# Light2021.net
KiCad netlist of a schematic drawn in EAGLE
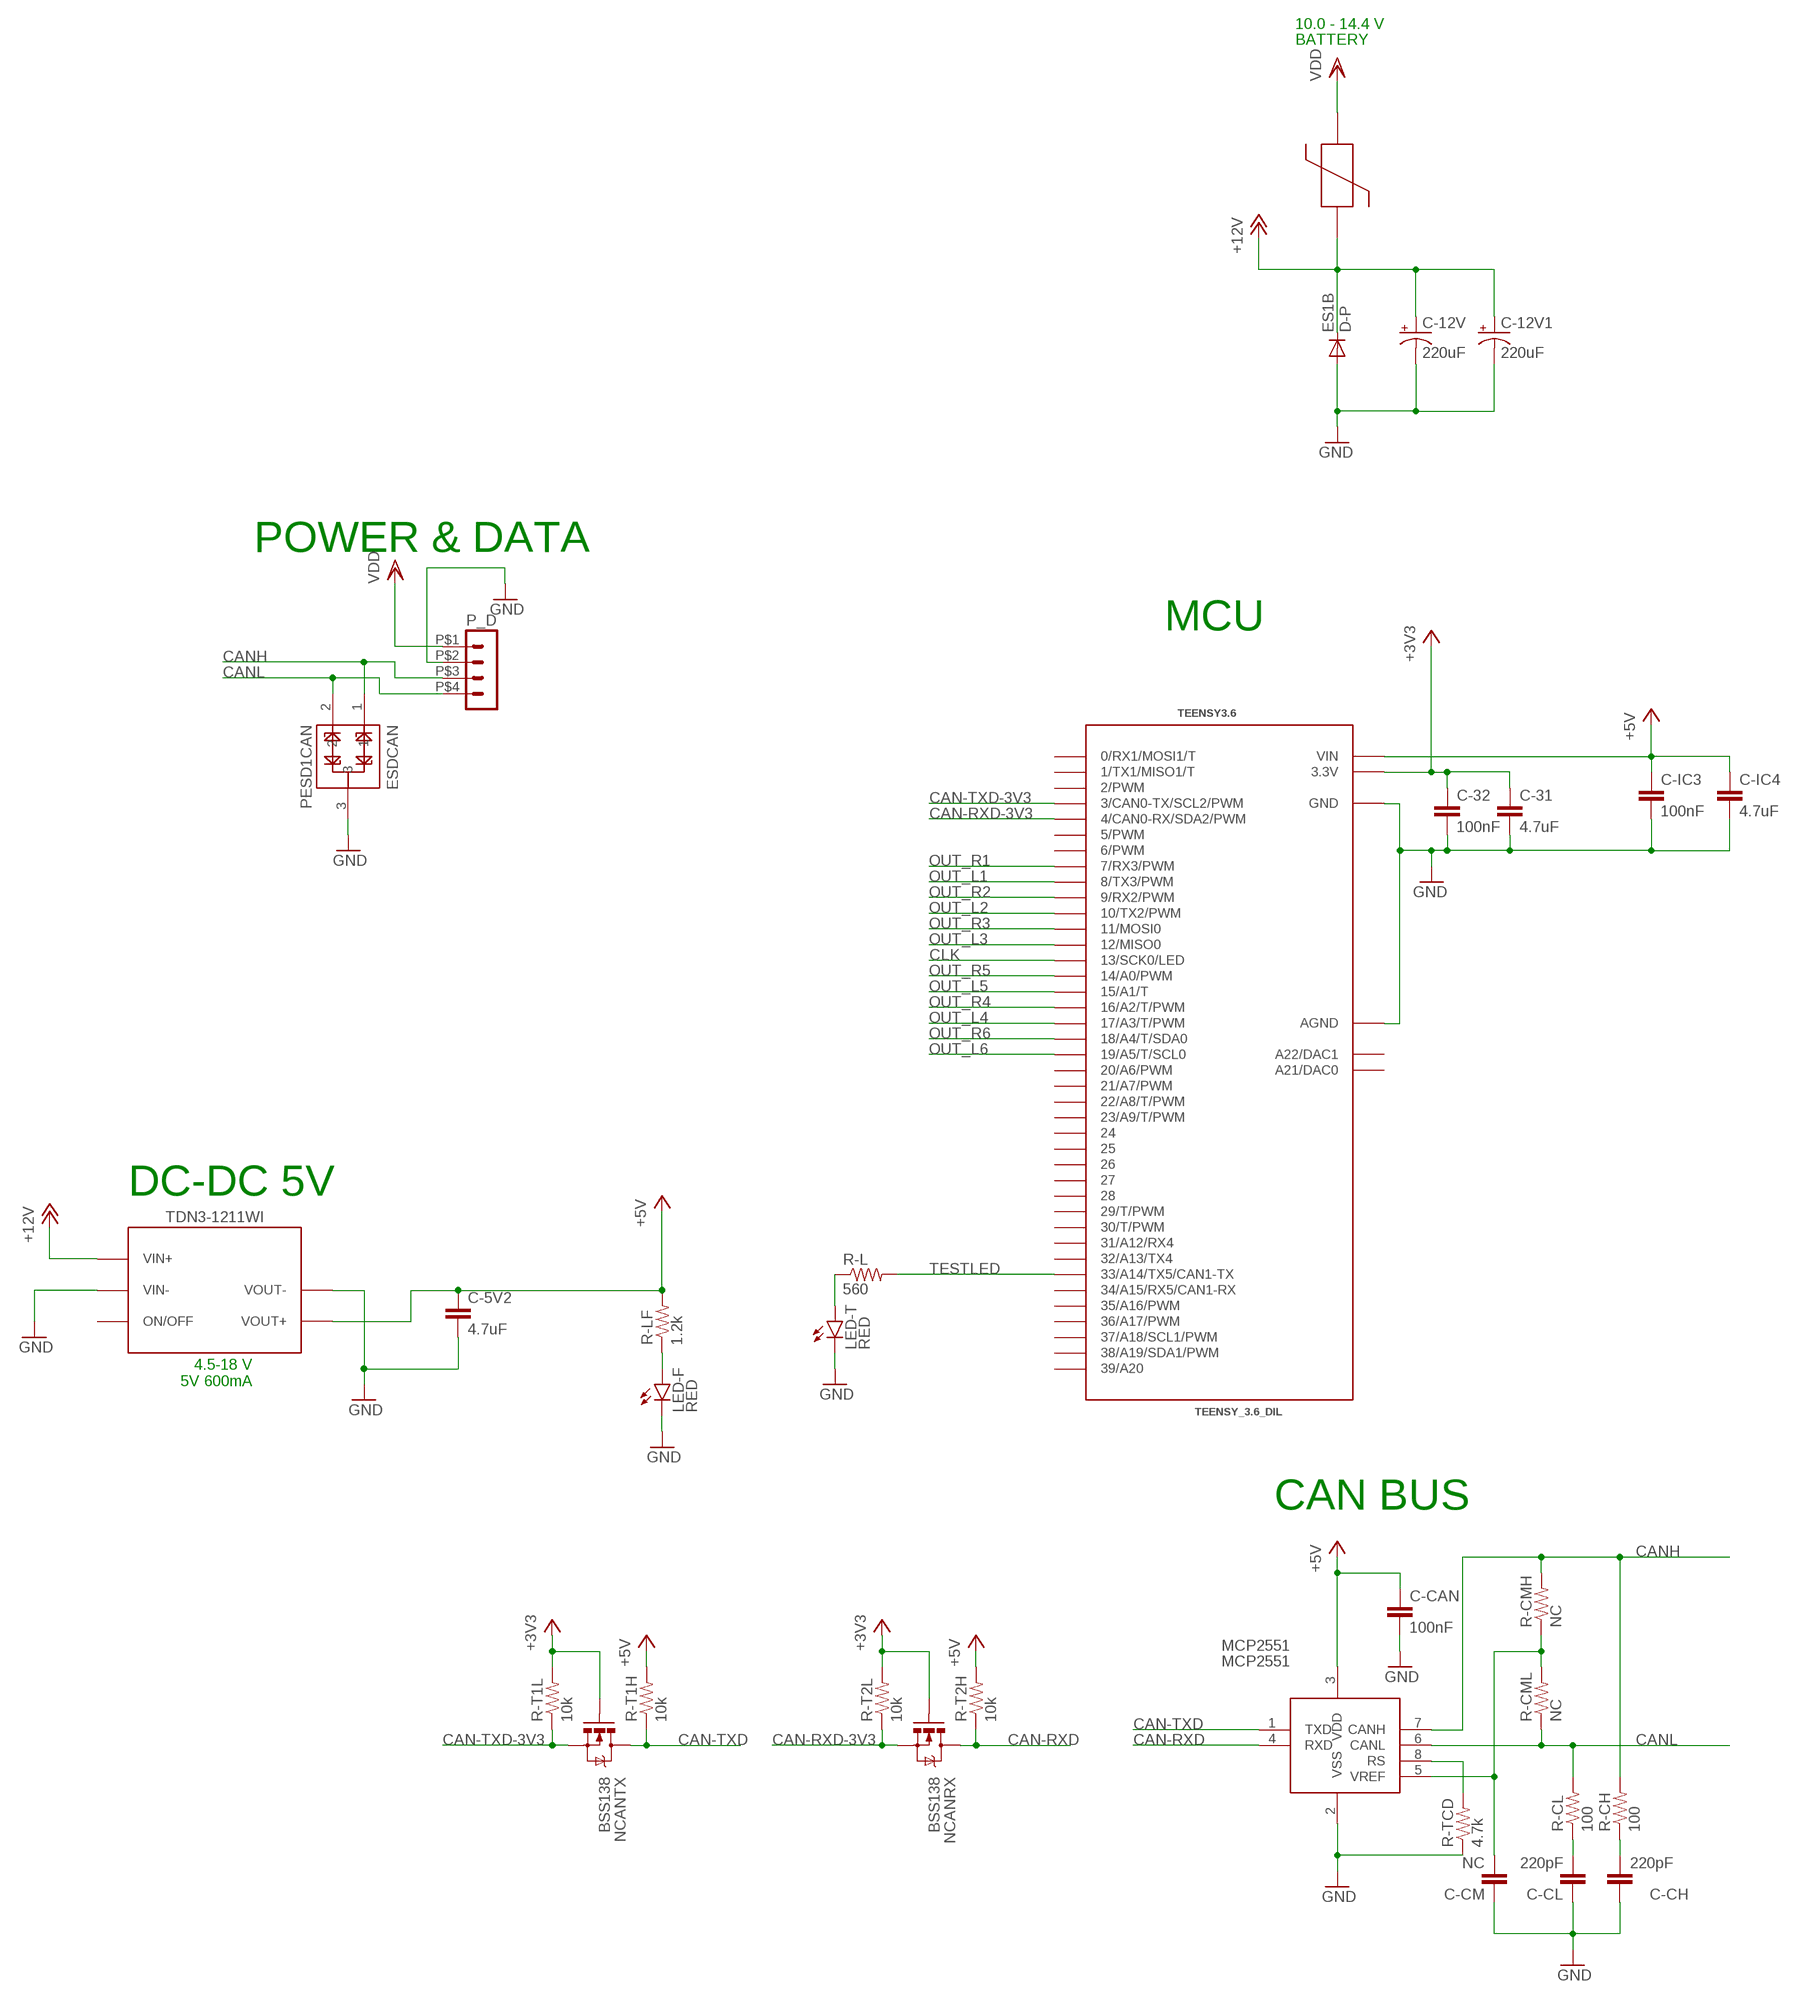
[diagram p0: schematic, sheet 1, part 1 of 2]
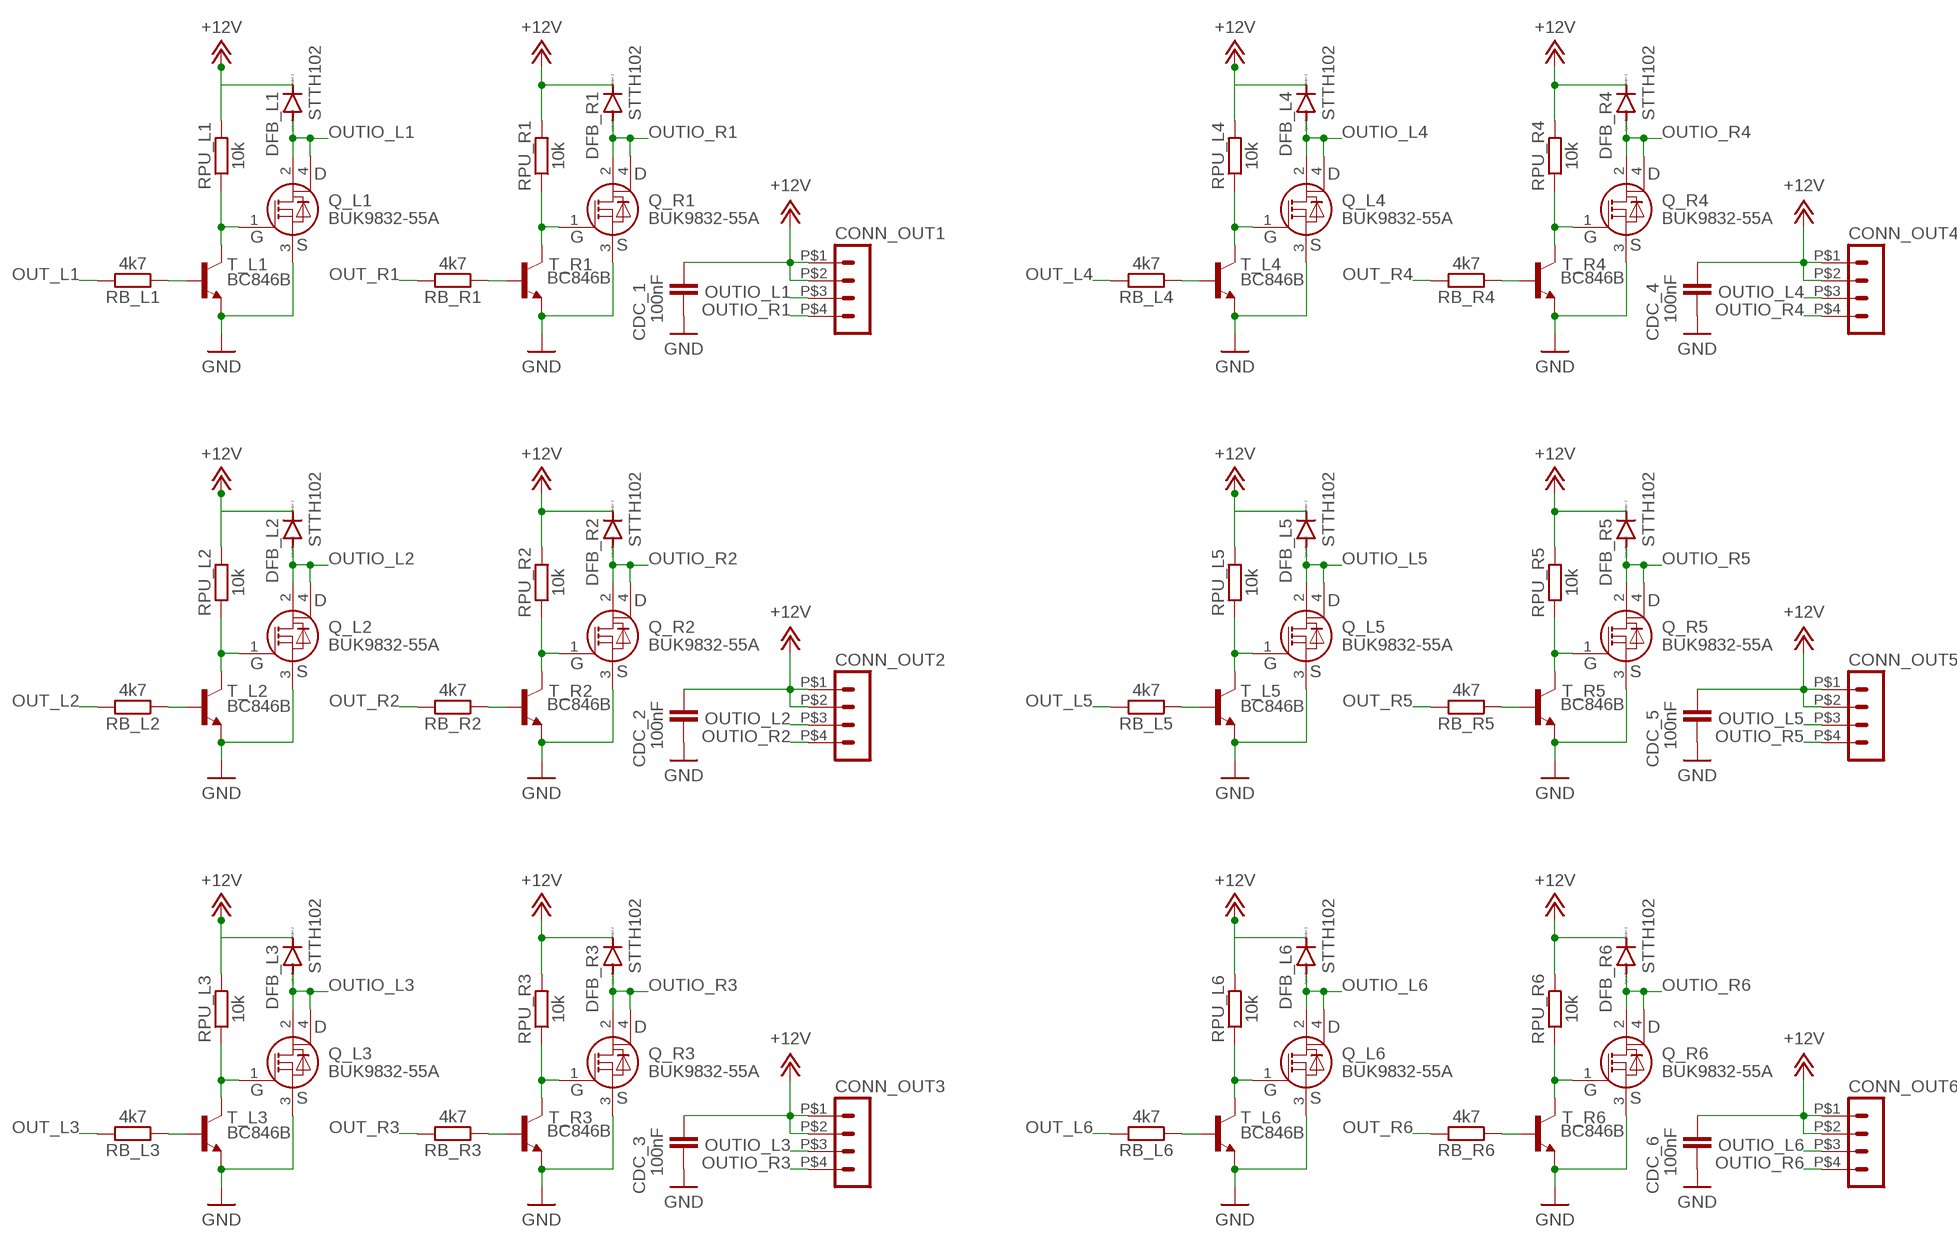
[diagram p1: schematic, sheet 1, part 2 of 2]

(export (version "E")
  (design (tool "Eeschema 10.0.6"))
  (components
    (comp (ref "C-5V2")
      (value "4.7uF")
      (footprint "eagle-import:1210")
      (libsource (lib "eagle-import") (part "CAP1210"))
    )
    (comp (ref "C-12V")
      (value "220uF")
      (footprint "eagle-import:PANASONIC_D")
      (libsource (lib "eagle-import") (part "CPOL-USD"))
    )
    (comp (ref "C-12V1")
      (value "220uF")
      (footprint "eagle-import:PANASONIC_D")
      (libsource (lib "eagle-import") (part "CPOL-USD"))
    )
    (comp (ref "C-31")
      (value "4.7uF")
      (footprint "eagle-import:1210")
      (libsource (lib "eagle-import") (part "CAP1210"))
    )
    (comp (ref "C-32")
      (value "100nF")
      (footprint "eagle-import:0805")
      (libsource (lib "eagle-import") (part "CAP0805"))
    )
    (comp (ref "C-CAN")
      (value "100nF")
      (footprint "eagle-import:0805")
      (libsource (lib "eagle-import") (part "CAP0805"))
    )
    (comp (ref "C-CH")
      (value "220pF")
      (footprint "eagle-import:0805")
      (libsource (lib "eagle-import") (part "CAP0805"))
    )
    (comp (ref "C-CL")
      (value "220pF")
      (footprint "eagle-import:0805")
      (libsource (lib "eagle-import") (part "CAP0805"))
    )
    (comp (ref "C-CM")
      (value "NC")
      (footprint "eagle-import:0805")
      (libsource (lib "eagle-import") (part "CAP0805"))
    )
    (comp (ref "C-IC3")
      (value "100nF")
      (footprint "eagle-import:0805")
      (libsource (lib "eagle-import") (part "CAP0805"))
    )
    (comp (ref "C-IC4")
      (value "4.7uF")
      (footprint "eagle-import:1210")
      (libsource (lib "eagle-import") (part "CAP1210"))
    )
    (comp (ref "CDC_1")
      (value "100nF")
      (footprint "eagle-import:0805")
      (libsource (lib "eagle-import") (part "CAP0805"))
    )
    (comp (ref "CDC_2")
      (value "100nF")
      (footprint "eagle-import:0805")
      (libsource (lib "eagle-import") (part "CAP0805"))
    )
    (comp (ref "CDC_3")
      (value "100nF")
      (footprint "eagle-import:0805")
      (libsource (lib "eagle-import") (part "CAP0805"))
    )
    (comp (ref "CDC_4")
      (value "100nF")
      (footprint "eagle-import:0805")
      (libsource (lib "eagle-import") (part "CAP0805"))
    )
    (comp (ref "CDC_5")
      (value "100nF")
      (footprint "eagle-import:0805")
      (libsource (lib "eagle-import") (part "CAP0805"))
    )
    (comp (ref "CDC_6")
      (value "100nF")
      (footprint "eagle-import:0805")
      (libsource (lib "eagle-import") (part "CAP0805"))
    )
    (comp (ref "CONN_OUT1")
      (value "HEADER_POS4_43045-0401")
      (footprint "eagle-import:43045-0400")
      (libsource (lib "eagle-import") (part "HEADER_POS4_?43045-0401"))
    )
    (comp (ref "CONN_OUT2")
      (value "HEADER_POS4_43045-0401")
      (footprint "eagle-import:43045-0400")
      (libsource (lib "eagle-import") (part "HEADER_POS4_?43045-0401"))
    )
    (comp (ref "CONN_OUT3")
      (value "HEADER_POS4_43045-0401")
      (footprint "eagle-import:43045-0400")
      (libsource (lib "eagle-import") (part "HEADER_POS4_?43045-0401"))
    )
    (comp (ref "CONN_OUT4")
      (value "HEADER_POS4_43045-0401")
      (footprint "eagle-import:43045-0400")
      (libsource (lib "eagle-import") (part "HEADER_POS4_?43045-0401"))
    )
    (comp (ref "CONN_OUT5")
      (value "HEADER_POS4_43045-0401")
      (footprint "eagle-import:43045-0400")
      (libsource (lib "eagle-import") (part "HEADER_POS4_?43045-0401"))
    )
    (comp (ref "CONN_OUT6")
      (value "HEADER_POS4_43045-0401")
      (footprint "eagle-import:43045-0400")
      (libsource (lib "eagle-import") (part "HEADER_POS4_?43045-0401"))
    )
    (comp (ref "D-P")
      (value "ES1B")
      (footprint "eagle-import:SMA-DIODE")
      (libsource (lib "eagle-import") (part "DIODESMA"))
    )
    (comp (ref "DFB_L1")
      (value "STTH102")
      (footprint "eagle-import:DO214AC")
      (libsource (lib "eagle-import") (part "DIODE-DO214AC"))
    )
    (comp (ref "DFB_L2")
      (value "STTH102")
      (footprint "eagle-import:DO214AC")
      (libsource (lib "eagle-import") (part "DIODE-DO214AC"))
    )
    (comp (ref "DFB_L3")
      (value "STTH102")
      (footprint "eagle-import:DO214AC")
      (libsource (lib "eagle-import") (part "DIODE-DO214AC"))
    )
    (comp (ref "DFB_L4")
      (value "STTH102")
      (footprint "eagle-import:DO214AC")
      (libsource (lib "eagle-import") (part "DIODE-DO214AC"))
    )
    (comp (ref "DFB_L5")
      (value "STTH102")
      (footprint "eagle-import:DO214AC")
      (libsource (lib "eagle-import") (part "DIODE-DO214AC"))
    )
    (comp (ref "DFB_L6")
      (value "STTH102")
      (footprint "eagle-import:DO214AC")
      (libsource (lib "eagle-import") (part "DIODE-DO214AC"))
    )
    (comp (ref "DFB_R1")
      (value "STTH102")
      (footprint "eagle-import:DO214AC")
      (libsource (lib "eagle-import") (part "DIODE-DO214AC"))
    )
    (comp (ref "DFB_R2")
      (value "STTH102")
      (footprint "eagle-import:DO214AC")
      (libsource (lib "eagle-import") (part "DIODE-DO214AC"))
    )
    (comp (ref "DFB_R3")
      (value "STTH102")
      (footprint "eagle-import:DO214AC")
      (libsource (lib "eagle-import") (part "DIODE-DO214AC"))
    )
    (comp (ref "DFB_R4")
      (value "STTH102")
      (footprint "eagle-import:DO214AC")
      (libsource (lib "eagle-import") (part "DIODE-DO214AC"))
    )
    (comp (ref "DFB_R5")
      (value "STTH102")
      (footprint "eagle-import:DO214AC")
      (libsource (lib "eagle-import") (part "DIODE-DO214AC"))
    )
    (comp (ref "DFB_R6")
      (value "STTH102")
      (footprint "eagle-import:DO214AC")
      (libsource (lib "eagle-import") (part "DIODE-DO214AC"))
    )
    (comp (ref "ESDCAN")
      (value "PESD1CAN")
      (footprint "eagle-import:SOT23-3")
      (libsource (lib "eagle-import") (part "PESD1CAN"))
    )
    (comp (ref "LED-F")
      (value "RED")
      (footprint "eagle-import:LED-1206")
      (libsource (lib "eagle-import") (part "LED1206"))
    )
    (comp (ref "LED-T")
      (value "RED")
      (footprint "eagle-import:LED-1206")
      (libsource (lib "eagle-import") (part "LED1206"))
    )
    (comp (ref "MAIN_FUSE")
      (value "SMF_OMNI-BLOK_FUSE_BLOCK")
      (footprint "eagle-import:SMF_OMNI-BLOK_FUSE_BLOCK")
      (libsource (lib "eagle-import") (part "SMF_OMNI-BLOK_FUSE_BLOCK"))
    )
    (comp (ref "MCP2551")
      (value "MCP2551")
      (footprint "eagle-import:SO-08M")
      (libsource (lib "eagle-import") (part "MCP2551"))
    )
    (comp (ref "NCANRX")
      (value "BSS138")
      (footprint "eagle-import:SOT23")
      (libsource (lib "eagle-import") (part "MOSFET-NCHANNELBSS123LT1G"))
    )
    (comp (ref "NCANTX")
      (value "BSS138")
      (footprint "eagle-import:SOT23")
      (libsource (lib "eagle-import") (part "MOSFET-NCHANNELBSS123LT1G"))
    )
    (comp (ref "P_D")
      (value "HEADER_POS4_43045-0401")
      (footprint "eagle-import:43045-0400")
      (libsource (lib "eagle-import") (part "HEADER_POS4_?43045-0401"))
    )
    (comp (ref "Q_L1")
      (value "BUK9832-55A")
      (footprint "eagle-import:SOT230P700X180-4N")
      (fields
        (field (name "MANUFACTURER_PART_NUMBER") "BUK9832-55A/CUX")
        (field (name "MOUSER_PART_NUMBER") "771-BUK9832-55A/CUX")
      )
      (libsource (lib "eagle-import") (part "BUK9832-55A"))
    )
    (comp (ref "Q_L2")
      (value "BUK9832-55A")
      (footprint "eagle-import:SOT230P700X180-4N")
      (fields
        (field (name "MANUFACTURER_PART_NUMBER") "BUK9832-55A/CUX")
        (field (name "MOUSER_PART_NUMBER") "771-BUK9832-55A/CUX")
      )
      (libsource (lib "eagle-import") (part "BUK9832-55A"))
    )
    (comp (ref "Q_L3")
      (value "BUK9832-55A")
      (footprint "eagle-import:SOT230P700X180-4N")
      (fields
        (field (name "MANUFACTURER_PART_NUMBER") "BUK9832-55A/CUX")
        (field (name "MOUSER_PART_NUMBER") "771-BUK9832-55A/CUX")
      )
      (libsource (lib "eagle-import") (part "BUK9832-55A"))
    )
    (comp (ref "Q_L4")
      (value "BUK9832-55A")
      (footprint "eagle-import:SOT230P700X180-4N")
      (fields
        (field (name "MANUFACTURER_PART_NUMBER") "BUK9832-55A/CUX")
        (field (name "MOUSER_PART_NUMBER") "771-BUK9832-55A/CUX")
      )
      (libsource (lib "eagle-import") (part "BUK9832-55A"))
    )
    (comp (ref "Q_L5")
      (value "BUK9832-55A")
      (footprint "eagle-import:SOT230P700X180-4N")
      (fields
        (field (name "MANUFACTURER_PART_NUMBER") "BUK9832-55A/CUX")
        (field (name "MOUSER_PART_NUMBER") "771-BUK9832-55A/CUX")
      )
      (libsource (lib "eagle-import") (part "BUK9832-55A"))
    )
    (comp (ref "Q_L6")
      (value "BUK9832-55A")
      (footprint "eagle-import:SOT230P700X180-4N")
      (fields
        (field (name "MANUFACTURER_PART_NUMBER") "BUK9832-55A/CUX")
        (field (name "MOUSER_PART_NUMBER") "771-BUK9832-55A/CUX")
      )
      (libsource (lib "eagle-import") (part "BUK9832-55A"))
    )
    (comp (ref "Q_R1")
      (value "BUK9832-55A")
      (footprint "eagle-import:SOT230P700X180-4N")
      (fields
        (field (name "MANUFACTURER_PART_NUMBER") "BUK9832-55A/CUX")
        (field (name "MOUSER_PART_NUMBER") "771-BUK9832-55A/CUX")
      )
      (libsource (lib "eagle-import") (part "BUK9832-55A"))
    )
    (comp (ref "Q_R2")
      (value "BUK9832-55A")
      (footprint "eagle-import:SOT230P700X180-4N")
      (fields
        (field (name "MANUFACTURER_PART_NUMBER") "BUK9832-55A/CUX")
        (field (name "MOUSER_PART_NUMBER") "771-BUK9832-55A/CUX")
      )
      (libsource (lib "eagle-import") (part "BUK9832-55A"))
    )
    (comp (ref "Q_R3")
      (value "BUK9832-55A")
      (footprint "eagle-import:SOT230P700X180-4N")
      (fields
        (field (name "MANUFACTURER_PART_NUMBER") "BUK9832-55A/CUX")
        (field (name "MOUSER_PART_NUMBER") "771-BUK9832-55A/CUX")
      )
      (libsource (lib "eagle-import") (part "BUK9832-55A"))
    )
    (comp (ref "Q_R4")
      (value "BUK9832-55A")
      (footprint "eagle-import:SOT230P700X180-4N")
      (fields
        (field (name "MANUFACTURER_PART_NUMBER") "BUK9832-55A/CUX")
        (field (name "MOUSER_PART_NUMBER") "771-BUK9832-55A/CUX")
      )
      (libsource (lib "eagle-import") (part "BUK9832-55A"))
    )
    (comp (ref "Q_R5")
      (value "BUK9832-55A")
      (footprint "eagle-import:SOT230P700X180-4N")
      (fields
        (field (name "MANUFACTURER_PART_NUMBER") "BUK9832-55A/CUX")
        (field (name "MOUSER_PART_NUMBER") "771-BUK9832-55A/CUX")
      )
      (libsource (lib "eagle-import") (part "BUK9832-55A"))
    )
    (comp (ref "Q_R6")
      (value "BUK9832-55A")
      (footprint "eagle-import:SOT230P700X180-4N")
      (fields
        (field (name "MANUFACTURER_PART_NUMBER") "BUK9832-55A/CUX")
        (field (name "MOUSER_PART_NUMBER") "771-BUK9832-55A/CUX")
      )
      (libsource (lib "eagle-import") (part "BUK9832-55A"))
    )
    (comp (ref "R-CH")
      (value "100")
      (footprint "eagle-import:0805")
      (libsource (lib "eagle-import") (part "RESISTOR0805"))
    )
    (comp (ref "R-CL")
      (value "100")
      (footprint "eagle-import:0805")
      (libsource (lib "eagle-import") (part "RESISTOR0805"))
    )
    (comp (ref "R-CMH")
      (value "NC")
      (footprint "eagle-import:0805")
      (libsource (lib "eagle-import") (part "RESISTOR0805"))
    )
    (comp (ref "R-CML")
      (value "NC")
      (footprint "eagle-import:0805")
      (libsource (lib "eagle-import") (part "RESISTOR0805"))
    )
    (comp (ref "R-L")
      (value "560")
      (footprint "eagle-import:0805")
      (libsource (lib "eagle-import") (part "RESISTOR0805"))
    )
    (comp (ref "R-LF")
      (value "1.2k")
      (footprint "eagle-import:0805")
      (libsource (lib "eagle-import") (part "RESISTOR0805"))
    )
    (comp (ref "R-T1H")
      (value "10k")
      (footprint "eagle-import:0805")
      (libsource (lib "eagle-import") (part "RESISTOR0805"))
    )
    (comp (ref "R-T1L")
      (value "10k")
      (footprint "eagle-import:0805")
      (libsource (lib "eagle-import") (part "RESISTOR0805"))
    )
    (comp (ref "R-T2H")
      (value "10k")
      (footprint "eagle-import:0805")
      (libsource (lib "eagle-import") (part "RESISTOR0805"))
    )
    (comp (ref "R-T2L")
      (value "10k")
      (footprint "eagle-import:0805")
      (libsource (lib "eagle-import") (part "RESISTOR0805"))
    )
    (comp (ref "R-TCD")
      (value "4.7k")
      (footprint "eagle-import:0805")
      (libsource (lib "eagle-import") (part "RESISTOR0805"))
    )
    (comp (ref "RB_L1")
      (value "4k7")
      (footprint "eagle-import:R0805")
      (libsource (lib "eagle-import") (part "R-EU_R0805"))
    )
    (comp (ref "RB_L2")
      (value "4k7")
      (footprint "eagle-import:R0805")
      (libsource (lib "eagle-import") (part "R-EU_R0805"))
    )
    (comp (ref "RB_L3")
      (value "4k7")
      (footprint "eagle-import:R0805")
      (libsource (lib "eagle-import") (part "R-EU_R0805"))
    )
    (comp (ref "RB_L4")
      (value "4k7")
      (footprint "eagle-import:R0805")
      (libsource (lib "eagle-import") (part "R-EU_R0805"))
    )
    (comp (ref "RB_L5")
      (value "4k7")
      (footprint "eagle-import:R0805")
      (libsource (lib "eagle-import") (part "R-EU_R0805"))
    )
    (comp (ref "RB_L6")
      (value "4k7")
      (footprint "eagle-import:R0805")
      (libsource (lib "eagle-import") (part "R-EU_R0805"))
    )
    (comp (ref "RB_R1")
      (value "4k7")
      (footprint "eagle-import:R0805")
      (libsource (lib "eagle-import") (part "R-EU_R0805"))
    )
    (comp (ref "RB_R2")
      (value "4k7")
      (footprint "eagle-import:R0805")
      (libsource (lib "eagle-import") (part "R-EU_R0805"))
    )
    (comp (ref "RB_R3")
      (value "4k7")
      (footprint "eagle-import:R0805")
      (libsource (lib "eagle-import") (part "R-EU_R0805"))
    )
    (comp (ref "RB_R4")
      (value "4k7")
      (footprint "eagle-import:R0805")
      (libsource (lib "eagle-import") (part "R-EU_R0805"))
    )
    (comp (ref "RB_R5")
      (value "4k7")
      (footprint "eagle-import:R0805")
      (libsource (lib "eagle-import") (part "R-EU_R0805"))
    )
    (comp (ref "RB_R6")
      (value "4k7")
      (footprint "eagle-import:R0805")
      (libsource (lib "eagle-import") (part "R-EU_R0805"))
    )
    (comp (ref "RPU_L1")
      (value "10k")
      (footprint "eagle-import:R0805")
      (libsource (lib "eagle-import") (part "R-EU_R0805"))
    )
    (comp (ref "RPU_L2")
      (value "10k")
      (footprint "eagle-import:R0805")
      (libsource (lib "eagle-import") (part "R-EU_R0805"))
    )
    (comp (ref "RPU_L3")
      (value "10k")
      (footprint "eagle-import:R0805")
      (libsource (lib "eagle-import") (part "R-EU_R0805"))
    )
    (comp (ref "RPU_L4")
      (value "10k")
      (footprint "eagle-import:R0805")
      (libsource (lib "eagle-import") (part "R-EU_R0805"))
    )
    (comp (ref "RPU_L5")
      (value "10k")
      (footprint "eagle-import:R0805")
      (libsource (lib "eagle-import") (part "R-EU_R0805"))
    )
    (comp (ref "RPU_L6")
      (value "10k")
      (footprint "eagle-import:R0805")
      (libsource (lib "eagle-import") (part "R-EU_R0805"))
    )
    (comp (ref "RPU_R1")
      (value "10k")
      (footprint "eagle-import:R0805")
      (libsource (lib "eagle-import") (part "R-EU_R0805"))
    )
    (comp (ref "RPU_R2")
      (value "10k")
      (footprint "eagle-import:R0805")
      (libsource (lib "eagle-import") (part "R-EU_R0805"))
    )
    (comp (ref "RPU_R3")
      (value "10k")
      (footprint "eagle-import:R0805")
      (libsource (lib "eagle-import") (part "R-EU_R0805"))
    )
    (comp (ref "RPU_R4")
      (value "10k")
      (footprint "eagle-import:R0805")
      (libsource (lib "eagle-import") (part "R-EU_R0805"))
    )
    (comp (ref "RPU_R5")
      (value "10k")
      (footprint "eagle-import:R0805")
      (libsource (lib "eagle-import") (part "R-EU_R0805"))
    )
    (comp (ref "RPU_R6")
      (value "10k")
      (footprint "eagle-import:R0805")
      (libsource (lib "eagle-import") (part "R-EU_R0805"))
    )
    (comp (ref "TDN3-1211WI")
      (value "TDN3WI")
      (footprint "eagle-import:TDC3WI")
      (libsource (lib "eagle-import") (part "TDN3WI"))
    )
    (comp (ref "TEENSY3.6")
      (value "TEENSY_3.6_DIL")
      (footprint "eagle-import:TEENSY_3.6_DIL")
      (libsource (lib "eagle-import") (part "TEENSY_3.6_DIL"))
    )
    (comp (ref "T_L1")
      (value "BC846B")
      (footprint "eagle-import:SOT23-BEC")
      (libsource (lib "eagle-import") (part "-NPN-SOT23-BECBC846B"))
    )
    (comp (ref "T_L2")
      (value "BC846B")
      (footprint "eagle-import:SOT23-BEC")
      (libsource (lib "eagle-import") (part "-NPN-SOT23-BECBC846B"))
    )
    (comp (ref "T_L3")
      (value "BC846B")
      (footprint "eagle-import:SOT23-BEC")
      (libsource (lib "eagle-import") (part "-NPN-SOT23-BECBC846B"))
    )
    (comp (ref "T_L4")
      (value "BC846B")
      (footprint "eagle-import:SOT23-BEC")
      (libsource (lib "eagle-import") (part "-NPN-SOT23-BECBC846B"))
    )
    (comp (ref "T_L5")
      (value "BC846B")
      (footprint "eagle-import:SOT23-BEC")
      (libsource (lib "eagle-import") (part "-NPN-SOT23-BECBC846B"))
    )
    (comp (ref "T_L6")
      (value "BC846B")
      (footprint "eagle-import:SOT23-BEC")
      (libsource (lib "eagle-import") (part "-NPN-SOT23-BECBC846B"))
    )
    (comp (ref "T_R1")
      (value "BC846B")
      (footprint "eagle-import:SOT23-BEC")
      (libsource (lib "eagle-import") (part "-NPN-SOT23-BECBC846B"))
    )
    (comp (ref "T_R2")
      (value "BC846B")
      (footprint "eagle-import:SOT23-BEC")
      (libsource (lib "eagle-import") (part "-NPN-SOT23-BECBC846B"))
    )
    (comp (ref "T_R3")
      (value "BC846B")
      (footprint "eagle-import:SOT23-BEC")
      (libsource (lib "eagle-import") (part "-NPN-SOT23-BECBC846B"))
    )
    (comp (ref "T_R4")
      (value "BC846B")
      (footprint "eagle-import:SOT23-BEC")
      (libsource (lib "eagle-import") (part "-NPN-SOT23-BECBC846B"))
    )
    (comp (ref "T_R5")
      (value "BC846B")
      (footprint "eagle-import:SOT23-BEC")
      (libsource (lib "eagle-import") (part "-NPN-SOT23-BECBC846B"))
    )
    (comp (ref "T_R6")
      (value "BC846B")
      (footprint "eagle-import:SOT23-BEC")
      (libsource (lib "eagle-import") (part "-NPN-SOT23-BECBC846B"))
    )
  )
  (nets
    (net (code "1") (name "+3V3") (class "Default")
      (node (ref "C-31") (pin "1") (pinfunction "1_1") (pintype "passive"))
      (node (ref "C-32") (pin "1") (pinfunction "1_1") (pintype "passive"))
      (node (ref "NCANRX") (pin "1") (pinfunction "G_1") (pintype "passive"))
      (node (ref "NCANTX") (pin "1") (pinfunction "G_1") (pintype "passive"))
      (node (ref "R-T1L") (pin "2") (pinfunction "2_2") (pintype "passive"))
      (node (ref "R-T2L") (pin "2") (pinfunction "2_2") (pintype "passive"))
      (node (ref "TEENSY3.6") (pin "3.3V1") (pinfunction "3.3V_3.3V1") (pintype "power_in"))
      (node (ref "TEENSY3.6") (pin "3.3V2") (pinfunction "3.3V_3.3V2") (pintype "power_in"))
    )
    (net (code "2") (name "+5V") (class "Default")
      (node (ref "C-5V2") (pin "1") (pinfunction "1_1") (pintype "passive"))
      (node (ref "C-CAN") (pin "1") (pinfunction "1_1") (pintype "passive"))
      (node (ref "C-IC3") (pin "1") (pinfunction "1_1") (pintype "passive"))
      (node (ref "C-IC4") (pin "1") (pinfunction "1_1") (pintype "passive"))
      (node (ref "MCP2551") (pin "3") (pinfunction "VDD_3") (pintype "power_in"))
      (node (ref "R-LF") (pin "2") (pinfunction "2_2") (pintype "passive"))
      (node (ref "R-T1H") (pin "2") (pinfunction "2_2") (pintype "passive"))
      (node (ref "R-T2H") (pin "2") (pinfunction "2_2") (pintype "passive"))
      (node (ref "TDN3-1211WI") (pin "VOUT+") (pinfunction "VOUT+_VOUT+") (pintype "bidirectional"))
      (node (ref "TEENSY3.6") (pin "VIN") (pinfunction "VIN_VIN") (pintype "power_in"))
    )
    (net (code "3") (name "+12V") (class "Default")
      (node (ref "C-12V") (pin "+") (pinfunction "+_+") (pintype "passive"))
      (node (ref "C-12V1") (pin "+") (pinfunction "+_+") (pintype "passive"))
      (node (ref "CDC_1") (pin "1") (pinfunction "1_1") (pintype "passive"))
      (node (ref "CDC_2") (pin "1") (pinfunction "1_1") (pintype "passive"))
      (node (ref "CDC_3") (pin "1") (pinfunction "1_1") (pintype "passive"))
      (node (ref "CDC_4") (pin "1") (pinfunction "1_1") (pintype "passive"))
      (node (ref "CDC_5") (pin "1") (pinfunction "1_1") (pintype "passive"))
      (node (ref "CDC_6") (pin "1") (pinfunction "1_1") (pintype "passive"))
      (node (ref "CONN_OUT1") (pin "P$1") (pinfunction "1_P$1") (pintype "passive"))
      (node (ref "CONN_OUT1") (pin "P$2") (pinfunction "2_P$2") (pintype "passive"))
      (node (ref "CONN_OUT2") (pin "P$1") (pinfunction "1_P$1") (pintype "passive"))
      (node (ref "CONN_OUT2") (pin "P$2") (pinfunction "2_P$2") (pintype "passive"))
      (node (ref "CONN_OUT3") (pin "P$1") (pinfunction "1_P$1") (pintype "passive"))
      (node (ref "CONN_OUT3") (pin "P$2") (pinfunction "2_P$2") (pintype "passive"))
      (node (ref "CONN_OUT4") (pin "P$1") (pinfunction "1_P$1") (pintype "passive"))
      (node (ref "CONN_OUT4") (pin "P$2") (pinfunction "2_P$2") (pintype "passive"))
      (node (ref "CONN_OUT5") (pin "P$1") (pinfunction "1_P$1") (pintype "passive"))
      (node (ref "CONN_OUT5") (pin "P$2") (pinfunction "2_P$2") (pintype "passive"))
      (node (ref "CONN_OUT6") (pin "P$1") (pinfunction "1_P$1") (pintype "passive"))
      (node (ref "CONN_OUT6") (pin "P$2") (pinfunction "2_P$2") (pintype "passive"))
      (node (ref "D-P") (pin "C") (pinfunction "C_C") (pintype "passive"))
      (node (ref "DFB_L1") (pin "C") (pinfunction "C_C") (pintype "passive"))
      (node (ref "DFB_L2") (pin "C") (pinfunction "C_C") (pintype "passive"))
      (node (ref "DFB_L3") (pin "C") (pinfunction "C_C") (pintype "passive"))
      (node (ref "DFB_L4") (pin "C") (pinfunction "C_C") (pintype "passive"))
      (node (ref "DFB_L5") (pin "C") (pinfunction "C_C") (pintype "passive"))
      (node (ref "DFB_L6") (pin "C") (pinfunction "C_C") (pintype "passive"))
      (node (ref "DFB_R1") (pin "C") (pinfunction "C_C") (pintype "passive"))
      (node (ref "DFB_R2") (pin "C") (pinfunction "C_C") (pintype "passive"))
      (node (ref "DFB_R3") (pin "C") (pinfunction "C_C") (pintype "passive"))
      (node (ref "DFB_R4") (pin "C") (pinfunction "C_C") (pintype "passive"))
      (node (ref "DFB_R5") (pin "C") (pinfunction "C_C") (pintype "passive"))
      (node (ref "DFB_R6") (pin "C") (pinfunction "C_C") (pintype "passive"))
      (node (ref "MAIN_FUSE") (pin "PIN1") (pinfunction "PIN1_PIN1") (pintype "bidirectional"))
      (node (ref "RPU_L1") (pin "2") (pinfunction "2_2") (pintype "passive"))
      (node (ref "RPU_L2") (pin "2") (pinfunction "2_2") (pintype "passive"))
      (node (ref "RPU_L3") (pin "2") (pinfunction "2_2") (pintype "passive"))
      (node (ref "RPU_L4") (pin "2") (pinfunction "2_2") (pintype "passive"))
      (node (ref "RPU_L5") (pin "2") (pinfunction "2_2") (pintype "passive"))
      (node (ref "RPU_L6") (pin "2") (pinfunction "2_2") (pintype "passive"))
      (node (ref "RPU_R1") (pin "2") (pinfunction "2_2") (pintype "passive"))
      (node (ref "RPU_R2") (pin "2") (pinfunction "2_2") (pintype "passive"))
      (node (ref "RPU_R3") (pin "2") (pinfunction "2_2") (pintype "passive"))
      (node (ref "RPU_R4") (pin "2") (pinfunction "2_2") (pintype "passive"))
      (node (ref "RPU_R5") (pin "2") (pinfunction "2_2") (pintype "passive"))
      (node (ref "RPU_R6") (pin "2") (pinfunction "2_2") (pintype "passive"))
      (node (ref "TDN3-1211WI") (pin "VIN+") (pinfunction "VIN+_VIN+") (pintype "bidirectional"))
    )
    (net (code "4") (name "/CAN-RXD") (class "Default")
      (node (ref "MCP2551") (pin "4") (pinfunction "RXD_4") (pintype "bidirectional"))
      (node (ref "NCANRX") (pin "3") (pinfunction "D_3") (pintype "passive"))
      (node (ref "R-T2H") (pin "1") (pinfunction "1_1") (pintype "passive"))
    )
    (net (code "5") (name "/CAN-RXD-3V3") (class "Default")
      (node (ref "NCANRX") (pin "2") (pinfunction "S_2") (pintype "passive"))
      (node (ref "R-T2L") (pin "1") (pinfunction "1_1") (pintype "passive"))
      (node (ref "TEENSY3.6") (pin "4") (pinfunction "4/CAN0-RX/SDA2/PWM_4") (pintype "bidirectional"))
    )
    (net (code "6") (name "/CAN-TXD") (class "Default")
      (node (ref "MCP2551") (pin "1") (pinfunction "TXD_1") (pintype "bidirectional"))
      (node (ref "NCANTX") (pin "3") (pinfunction "D_3") (pintype "passive"))
      (node (ref "R-T1H") (pin "1") (pinfunction "1_1") (pintype "passive"))
    )
    (net (code "7") (name "/CAN-TXD-3V3") (class "Default")
      (node (ref "NCANTX") (pin "2") (pinfunction "S_2") (pintype "passive"))
      (node (ref "R-T1L") (pin "1") (pinfunction "1_1") (pintype "passive"))
      (node (ref "TEENSY3.6") (pin "3") (pinfunction "3/CAN0-TX/SCL2/PWM_3") (pintype "bidirectional"))
    )
    (net (code "8") (name "/CANH") (class "Default")
      (node (ref "ESDCAN") (pin "1") (pinfunction "1_1") (pintype "bidirectional"))
      (node (ref "MCP2551") (pin "7") (pinfunction "CANH_7") (pintype "bidirectional"))
      (node (ref "P_D") (pin "P$3") (pinfunction "3_P$3") (pintype "passive"))
      (node (ref "R-CH") (pin "2") (pinfunction "2_2") (pintype "passive"))
      (node (ref "R-CMH") (pin "2") (pinfunction "2_2") (pintype "passive"))
    )
    (net (code "9") (name "/CANL") (class "Default")
      (node (ref "ESDCAN") (pin "2") (pinfunction "2_2") (pintype "bidirectional"))
      (node (ref "MCP2551") (pin "6") (pinfunction "CANL_6") (pintype "bidirectional"))
      (node (ref "P_D") (pin "P$4") (pinfunction "4_P$4") (pintype "passive"))
      (node (ref "R-CL") (pin "2") (pinfunction "2_2") (pintype "passive"))
      (node (ref "R-CML") (pin "1") (pinfunction "1_1") (pintype "passive"))
    )
    (net (code "10") (name "/CLK") (class "Default")
      (node (ref "TEENSY3.6") (pin "13") (pinfunction "13/SCK0/LED_13") (pintype "bidirectional"))
    )
    (net (code "11") (name "/OUTIO_L1") (class "Default")
      (node (ref "CONN_OUT1") (pin "P$3") (pinfunction "3_P$3") (pintype "passive"))
      (node (ref "DFB_L1") (pin "A") (pinfunction "A_A") (pintype "passive"))
      (node (ref "Q_L1") (pin "2") (pinfunction "D_2") (pintype "bidirectional"))
      (node (ref "Q_L1") (pin "4") (pinfunction "D_4") (pintype "bidirectional"))
    )
    (net (code "12") (name "/OUTIO_L2") (class "Default")
      (node (ref "CONN_OUT2") (pin "P$3") (pinfunction "3_P$3") (pintype "passive"))
      (node (ref "DFB_L2") (pin "A") (pinfunction "A_A") (pintype "passive"))
      (node (ref "Q_L2") (pin "2") (pinfunction "D_2") (pintype "bidirectional"))
      (node (ref "Q_L2") (pin "4") (pinfunction "D_4") (pintype "bidirectional"))
    )
    (net (code "13") (name "/OUTIO_L3") (class "Default")
      (node (ref "CONN_OUT3") (pin "P$3") (pinfunction "3_P$3") (pintype "passive"))
      (node (ref "DFB_L3") (pin "A") (pinfunction "A_A") (pintype "passive"))
      (node (ref "Q_L3") (pin "2") (pinfunction "D_2") (pintype "bidirectional"))
      (node (ref "Q_L3") (pin "4") (pinfunction "D_4") (pintype "bidirectional"))
    )
    (net (code "14") (name "/OUTIO_L4") (class "Default")
      (node (ref "CONN_OUT4") (pin "P$3") (pinfunction "3_P$3") (pintype "passive"))
      (node (ref "DFB_L4") (pin "A") (pinfunction "A_A") (pintype "passive"))
      (node (ref "Q_L4") (pin "2") (pinfunction "D_2") (pintype "bidirectional"))
      (node (ref "Q_L4") (pin "4") (pinfunction "D_4") (pintype "bidirectional"))
    )
    (net (code "15") (name "/OUTIO_L5") (class "Default")
      (node (ref "CONN_OUT5") (pin "P$3") (pinfunction "3_P$3") (pintype "passive"))
      (node (ref "DFB_L5") (pin "A") (pinfunction "A_A") (pintype "passive"))
      (node (ref "Q_L5") (pin "2") (pinfunction "D_2") (pintype "bidirectional"))
      (node (ref "Q_L5") (pin "4") (pinfunction "D_4") (pintype "bidirectional"))
    )
    (net (code "16") (name "/OUTIO_L6") (class "Default")
      (node (ref "CONN_OUT6") (pin "P$3") (pinfunction "3_P$3") (pintype "passive"))
      (node (ref "DFB_L6") (pin "A") (pinfunction "A_A") (pintype "passive"))
      (node (ref "Q_L6") (pin "2") (pinfunction "D_2") (pintype "bidirectional"))
      (node (ref "Q_L6") (pin "4") (pinfunction "D_4") (pintype "bidirectional"))
    )
    (net (code "17") (name "/OUTIO_R1") (class "Default")
      (node (ref "CONN_OUT1") (pin "P$4") (pinfunction "4_P$4") (pintype "passive"))
      (node (ref "DFB_R1") (pin "A") (pinfunction "A_A") (pintype "passive"))
      (node (ref "Q_R1") (pin "2") (pinfunction "D_2") (pintype "bidirectional"))
      (node (ref "Q_R1") (pin "4") (pinfunction "D_4") (pintype "bidirectional"))
    )
    (net (code "18") (name "/OUTIO_R2") (class "Default")
      (node (ref "CONN_OUT2") (pin "P$4") (pinfunction "4_P$4") (pintype "passive"))
      (node (ref "DFB_R2") (pin "A") (pinfunction "A_A") (pintype "passive"))
      (node (ref "Q_R2") (pin "2") (pinfunction "D_2") (pintype "bidirectional"))
      (node (ref "Q_R2") (pin "4") (pinfunction "D_4") (pintype "bidirectional"))
    )
    (net (code "19") (name "/OUTIO_R3") (class "Default")
      (node (ref "CONN_OUT3") (pin "P$4") (pinfunction "4_P$4") (pintype "passive"))
      (node (ref "DFB_R3") (pin "A") (pinfunction "A_A") (pintype "passive"))
      (node (ref "Q_R3") (pin "2") (pinfunction "D_2") (pintype "bidirectional"))
      (node (ref "Q_R3") (pin "4") (pinfunction "D_4") (pintype "bidirectional"))
    )
    (net (code "20") (name "/OUTIO_R4") (class "Default")
      (node (ref "CONN_OUT4") (pin "P$4") (pinfunction "4_P$4") (pintype "passive"))
      (node (ref "DFB_R4") (pin "A") (pinfunction "A_A") (pintype "passive"))
      (node (ref "Q_R4") (pin "2") (pinfunction "D_2") (pintype "bidirectional"))
      (node (ref "Q_R4") (pin "4") (pinfunction "D_4") (pintype "bidirectional"))
    )
    (net (code "21") (name "/OUTIO_R5") (class "Default")
      (node (ref "CONN_OUT5") (pin "P$4") (pinfunction "4_P$4") (pintype "passive"))
      (node (ref "DFB_R5") (pin "A") (pinfunction "A_A") (pintype "passive"))
      (node (ref "Q_R5") (pin "2") (pinfunction "D_2") (pintype "bidirectional"))
      (node (ref "Q_R5") (pin "4") (pinfunction "D_4") (pintype "bidirectional"))
    )
    (net (code "22") (name "/OUTIO_R6") (class "Default")
      (node (ref "CONN_OUT6") (pin "P$4") (pinfunction "4_P$4") (pintype "passive"))
      (node (ref "DFB_R6") (pin "A") (pinfunction "A_A") (pintype "passive"))
      (node (ref "Q_R6") (pin "2") (pinfunction "D_2") (pintype "bidirectional"))
      (node (ref "Q_R6") (pin "4") (pinfunction "D_4") (pintype "bidirectional"))
    )
    (net (code "23") (name "/OUT_L1") (class "Default")
      (node (ref "RB_L1") (pin "2") (pinfunction "2_2") (pintype "passive"))
      (node (ref "TEENSY3.6") (pin "8") (pinfunction "8/TX3/PWM_8") (pintype "bidirectional"))
    )
    (net (code "24") (name "/OUT_L2") (class "Default")
      (node (ref "RB_L2") (pin "2") (pinfunction "2_2") (pintype "passive"))
      (node (ref "TEENSY3.6") (pin "10") (pinfunction "10/TX2/PWM_10") (pintype "bidirectional"))
    )
    (net (code "25") (name "/OUT_L3") (class "Default")
      (node (ref "RB_L3") (pin "2") (pinfunction "2_2") (pintype "passive"))
      (node (ref "TEENSY3.6") (pin "12") (pinfunction "12/MISO0_12") (pintype "bidirectional"))
    )
    (net (code "26") (name "/OUT_L4") (class "Default")
      (node (ref "RB_L4") (pin "2") (pinfunction "2_2") (pintype "passive"))
      (node (ref "TEENSY3.6") (pin "17/A3") (pinfunction "17/A3/T/PWM_17/A3") (pintype "bidirectional"))
    )
    (net (code "27") (name "/OUT_L5") (class "Default")
      (node (ref "RB_L5") (pin "2") (pinfunction "2_2") (pintype "passive"))
      (node (ref "TEENSY3.6") (pin "15/A1") (pinfunction "15/A1/T_15/A1") (pintype "bidirectional"))
    )
    (net (code "28") (name "/OUT_L6") (class "Default")
      (node (ref "RB_L6") (pin "2") (pinfunction "2_2") (pintype "passive"))
      (node (ref "TEENSY3.6") (pin "19/A5") (pinfunction "19/A5/T/SCL0_19/A5") (pintype "bidirectional"))
    )
    (net (code "29") (name "/OUT_R1") (class "Default")
      (node (ref "RB_R1") (pin "2") (pinfunction "2_2") (pintype "passive"))
      (node (ref "TEENSY3.6") (pin "7") (pinfunction "7/RX3/PWM_7") (pintype "bidirectional"))
    )
    (net (code "30") (name "/OUT_R2") (class "Default")
      (node (ref "RB_R2") (pin "2") (pinfunction "2_2") (pintype "passive"))
      (node (ref "TEENSY3.6") (pin "9") (pinfunction "9/RX2/PWM_9") (pintype "bidirectional"))
    )
    (net (code "31") (name "/OUT_R3") (class "Default")
      (node (ref "RB_R3") (pin "2") (pinfunction "2_2") (pintype "passive"))
      (node (ref "TEENSY3.6") (pin "11") (pinfunction "11/MOSI0_11") (pintype "bidirectional"))
    )
    (net (code "32") (name "/OUT_R4") (class "Default")
      (node (ref "RB_R4") (pin "2") (pinfunction "2_2") (pintype "passive"))
      (node (ref "TEENSY3.6") (pin "16/A2") (pinfunction "16/A2/T/PWM_16/A2") (pintype "bidirectional"))
    )
    (net (code "33") (name "/OUT_R5") (class "Default")
      (node (ref "RB_R5") (pin "2") (pinfunction "2_2") (pintype "passive"))
      (node (ref "TEENSY3.6") (pin "14/A0") (pinfunction "14/A0/PWM_14/A0") (pintype "bidirectional"))
    )
    (net (code "34") (name "/OUT_R6") (class "Default")
      (node (ref "RB_R6") (pin "2") (pinfunction "2_2") (pintype "passive"))
      (node (ref "TEENSY3.6") (pin "18/A4") (pinfunction "18/A4/T/SDA0_18/A4") (pintype "bidirectional"))
    )
    (net (code "35") (name "/TESTLED") (class "Default")
      (node (ref "R-L") (pin "2") (pinfunction "2_2") (pintype "passive"))
      (node (ref "TEENSY3.6") (pin "33/A14") (pinfunction "33/A14/TX5/CAN1-TX_33/A14") (pintype "bidirectional"))
    )
    (net (code "36") (name "GND") (class "Default")
      (node (ref "C-12V") (pin "-") (pinfunction "-_-") (pintype "passive"))
      (node (ref "C-12V1") (pin "-") (pinfunction "-_-") (pintype "passive"))
      (node (ref "C-31") (pin "2") (pinfunction "2_2") (pintype "passive"))
      (node (ref "C-32") (pin "2") (pinfunction "2_2") (pintype "passive"))
      (node (ref "C-5V2") (pin "2") (pinfunction "2_2") (pintype "passive"))
      (node (ref "C-CAN") (pin "2") (pinfunction "2_2") (pintype "passive"))
      (node (ref "C-CH") (pin "1") (pinfunction "1_1") (pintype "passive"))
      (node (ref "C-CL") (pin "1") (pinfunction "1_1") (pintype "passive"))
      (node (ref "C-CM") (pin "1") (pinfunction "1_1") (pintype "passive"))
      (node (ref "C-IC3") (pin "2") (pinfunction "2_2") (pintype "passive"))
      (node (ref "C-IC4") (pin "2") (pinfunction "2_2") (pintype "passive"))
      (node (ref "CDC_1") (pin "2") (pinfunction "2_2") (pintype "passive"))
      (node (ref "CDC_2") (pin "2") (pinfunction "2_2") (pintype "passive"))
      (node (ref "CDC_3") (pin "2") (pinfunction "2_2") (pintype "passive"))
      (node (ref "CDC_4") (pin "2") (pinfunction "2_2") (pintype "passive"))
      (node (ref "CDC_5") (pin "2") (pinfunction "2_2") (pintype "passive"))
      (node (ref "CDC_6") (pin "2") (pinfunction "2_2") (pintype "passive"))
      (node (ref "D-P") (pin "A") (pinfunction "A_A") (pintype "passive"))
      (node (ref "ESDCAN") (pin "3") (pinfunction "3_3") (pintype "bidirectional"))
      (node (ref "LED-F") (pin "C") (pinfunction "C_C") (pintype "passive"))
      (node (ref "LED-T") (pin "C") (pinfunction "C_C") (pintype "passive"))
      (node (ref "MCP2551") (pin "2") (pinfunction "VSS_2") (pintype "power_in"))
      (node (ref "P_D") (pin "P$2") (pinfunction "2_P$2") (pintype "passive"))
      (node (ref "Q_L1") (pin "3") (pinfunction "S_3") (pintype "bidirectional"))
      (node (ref "Q_L2") (pin "3") (pinfunction "S_3") (pintype "bidirectional"))
      (node (ref "Q_L3") (pin "3") (pinfunction "S_3") (pintype "bidirectional"))
      (node (ref "Q_L4") (pin "3") (pinfunction "S_3") (pintype "bidirectional"))
      (node (ref "Q_L5") (pin "3") (pinfunction "S_3") (pintype "bidirectional"))
      (node (ref "Q_L6") (pin "3") (pinfunction "S_3") (pintype "bidirectional"))
      (node (ref "Q_R1") (pin "3") (pinfunction "S_3") (pintype "bidirectional"))
      (node (ref "Q_R2") (pin "3") (pinfunction "S_3") (pintype "bidirectional"))
      (node (ref "Q_R3") (pin "3") (pinfunction "S_3") (pintype "bidirectional"))
      (node (ref "Q_R4") (pin "3") (pinfunction "S_3") (pintype "bidirectional"))
      (node (ref "Q_R5") (pin "3") (pinfunction "S_3") (pintype "bidirectional"))
      (node (ref "Q_R6") (pin "3") (pinfunction "S_3") (pintype "bidirectional"))
      (node (ref "R-TCD") (pin "1") (pinfunction "1_1") (pintype "passive"))
      (node (ref "TDN3-1211WI") (pin "VIN-") (pinfunction "VIN-_VIN-") (pintype "bidirectional"))
      (node (ref "TDN3-1211WI") (pin "VOUT-") (pinfunction "VOUT-_VOUT-") (pintype "bidirectional"))
      (node (ref "TEENSY3.6") (pin "AGND") (pinfunction "AGND_AGND") (pintype "power_in"))
      (node (ref "TEENSY3.6") (pin "GND") (pinfunction "GND_GND") (pintype "power_in"))
      (node (ref "TEENSY3.6") (pin "GND1") (pinfunction "GND_GND1") (pintype "power_in"))
      (node (ref "T_L1") (pin "E") (pinfunction "E_E") (pintype "passive"))
      (node (ref "T_L2") (pin "E") (pinfunction "E_E") (pintype "passive"))
      (node (ref "T_L3") (pin "E") (pinfunction "E_E") (pintype "passive"))
      (node (ref "T_L4") (pin "E") (pinfunction "E_E") (pintype "passive"))
      (node (ref "T_L5") (pin "E") (pinfunction "E_E") (pintype "passive"))
      (node (ref "T_L6") (pin "E") (pinfunction "E_E") (pintype "passive"))
      (node (ref "T_R1") (pin "E") (pinfunction "E_E") (pintype "passive"))
      (node (ref "T_R2") (pin "E") (pinfunction "E_E") (pintype "passive"))
      (node (ref "T_R3") (pin "E") (pinfunction "E_E") (pintype "passive"))
      (node (ref "T_R4") (pin "E") (pinfunction "E_E") (pintype "passive"))
      (node (ref "T_R5") (pin "E") (pinfunction "E_E") (pintype "passive"))
      (node (ref "T_R6") (pin "E") (pinfunction "E_E") (pintype "passive"))
    )
    (net (code "37") (name "Net-(C-CH-Pad2)") (class "Default")
      (node (ref "C-CH") (pin "2") (pinfunction "2_2") (pintype "passive"))
      (node (ref "R-CH") (pin "1") (pinfunction "1_1") (pintype "passive"))
    )
    (net (code "38") (name "Net-(C-CL-Pad2)") (class "Default")
      (node (ref "C-CL") (pin "2") (pinfunction "2_2") (pintype "passive"))
      (node (ref "R-CL") (pin "1") (pinfunction "1_1") (pintype "passive"))
    )
    (net (code "39") (name "Net-(LED-F-PadA)") (class "Default")
      (node (ref "LED-F") (pin "A") (pinfunction "A_A") (pintype "passive"))
      (node (ref "R-LF") (pin "1") (pinfunction "1_1") (pintype "passive"))
    )
    (net (code "40") (name "Net-(LED-T-PadA)") (class "Default")
      (node (ref "LED-T") (pin "A") (pinfunction "A_A") (pintype "passive"))
      (node (ref "R-L") (pin "1") (pinfunction "1_1") (pintype "passive"))
    )
    (net (code "41") (name "Net-(MCP2551-RS)") (class "Default")
      (node (ref "MCP2551") (pin "8") (pinfunction "RS_8") (pintype "bidirectional"))
      (node (ref "R-TCD") (pin "2") (pinfunction "2_2") (pintype "passive"))
    )
    (net (code "42") (name "Net-(MCP2551-VREF)") (class "Default")
      (node (ref "C-CM") (pin "2") (pinfunction "2_2") (pintype "passive"))
      (node (ref "MCP2551") (pin "5") (pinfunction "VREF_5") (pintype "bidirectional"))
      (node (ref "R-CMH") (pin "1") (pinfunction "1_1") (pintype "passive"))
      (node (ref "R-CML") (pin "2") (pinfunction "2_2") (pintype "passive"))
    )
    (net (code "43") (name "Net-(Q_L1-G)") (class "Default")
      (node (ref "Q_L1") (pin "1") (pinfunction "G_1") (pintype "bidirectional"))
      (node (ref "RPU_L1") (pin "1") (pinfunction "1_1") (pintype "passive"))
      (node (ref "T_L1") (pin "C") (pinfunction "C_C") (pintype "passive"))
    )
    (net (code "44") (name "Net-(Q_L2-G)") (class "Default")
      (node (ref "Q_L2") (pin "1") (pinfunction "G_1") (pintype "bidirectional"))
      (node (ref "RPU_L2") (pin "1") (pinfunction "1_1") (pintype "passive"))
      (node (ref "T_L2") (pin "C") (pinfunction "C_C") (pintype "passive"))
    )
    (net (code "45") (name "Net-(Q_L3-G)") (class "Default")
      (node (ref "Q_L3") (pin "1") (pinfunction "G_1") (pintype "bidirectional"))
      (node (ref "RPU_L3") (pin "1") (pinfunction "1_1") (pintype "passive"))
      (node (ref "T_L3") (pin "C") (pinfunction "C_C") (pintype "passive"))
    )
    (net (code "46") (name "Net-(Q_L4-G)") (class "Default")
      (node (ref "Q_L4") (pin "1") (pinfunction "G_1") (pintype "bidirectional"))
      (node (ref "RPU_L4") (pin "1") (pinfunction "1_1") (pintype "passive"))
      (node (ref "T_L4") (pin "C") (pinfunction "C_C") (pintype "passive"))
    )
    (net (code "47") (name "Net-(Q_L5-G)") (class "Default")
      (node (ref "Q_L5") (pin "1") (pinfunction "G_1") (pintype "bidirectional"))
      (node (ref "RPU_L5") (pin "1") (pinfunction "1_1") (pintype "passive"))
      (node (ref "T_L5") (pin "C") (pinfunction "C_C") (pintype "passive"))
    )
    (net (code "48") (name "Net-(Q_L6-G)") (class "Default")
      (node (ref "Q_L6") (pin "1") (pinfunction "G_1") (pintype "bidirectional"))
      (node (ref "RPU_L6") (pin "1") (pinfunction "1_1") (pintype "passive"))
      (node (ref "T_L6") (pin "C") (pinfunction "C_C") (pintype "passive"))
    )
    (net (code "49") (name "Net-(Q_R1-G)") (class "Default")
      (node (ref "Q_R1") (pin "1") (pinfunction "G_1") (pintype "bidirectional"))
      (node (ref "RPU_R1") (pin "1") (pinfunction "1_1") (pintype "passive"))
      (node (ref "T_R1") (pin "C") (pinfunction "C_C") (pintype "passive"))
    )
    (net (code "50") (name "Net-(Q_R2-G)") (class "Default")
      (node (ref "Q_R2") (pin "1") (pinfunction "G_1") (pintype "bidirectional"))
      (node (ref "RPU_R2") (pin "1") (pinfunction "1_1") (pintype "passive"))
      (node (ref "T_R2") (pin "C") (pinfunction "C_C") (pintype "passive"))
    )
    (net (code "51") (name "Net-(Q_R3-G)") (class "Default")
      (node (ref "Q_R3") (pin "1") (pinfunction "G_1") (pintype "bidirectional"))
      (node (ref "RPU_R3") (pin "1") (pinfunction "1_1") (pintype "passive"))
      (node (ref "T_R3") (pin "C") (pinfunction "C_C") (pintype "passive"))
    )
    (net (code "52") (name "Net-(Q_R4-G)") (class "Default")
      (node (ref "Q_R4") (pin "1") (pinfunction "G_1") (pintype "bidirectional"))
      (node (ref "RPU_R4") (pin "1") (pinfunction "1_1") (pintype "passive"))
      (node (ref "T_R4") (pin "C") (pinfunction "C_C") (pintype "passive"))
    )
    (net (code "53") (name "Net-(Q_R5-G)") (class "Default")
      (node (ref "Q_R5") (pin "1") (pinfunction "G_1") (pintype "bidirectional"))
      (node (ref "RPU_R5") (pin "1") (pinfunction "1_1") (pintype "passive"))
      (node (ref "T_R5") (pin "C") (pinfunction "C_C") (pintype "passive"))
    )
    (net (code "54") (name "Net-(Q_R6-G)") (class "Default")
      (node (ref "Q_R6") (pin "1") (pinfunction "G_1") (pintype "bidirectional"))
      (node (ref "RPU_R6") (pin "1") (pinfunction "1_1") (pintype "passive"))
      (node (ref "T_R6") (pin "C") (pinfunction "C_C") (pintype "passive"))
    )
    (net (code "55") (name "Net-(RB_L1-Pad1)") (class "Default")
      (node (ref "RB_L1") (pin "1") (pinfunction "1_1") (pintype "passive"))
      (node (ref "T_L1") (pin "B") (pinfunction "B_B") (pintype "passive"))
    )
    (net (code "56") (name "Net-(RB_L2-Pad1)") (class "Default")
      (node (ref "RB_L2") (pin "1") (pinfunction "1_1") (pintype "passive"))
      (node (ref "T_L2") (pin "B") (pinfunction "B_B") (pintype "passive"))
    )
    (net (code "57") (name "Net-(RB_L3-Pad1)") (class "Default")
      (node (ref "RB_L3") (pin "1") (pinfunction "1_1") (pintype "passive"))
      (node (ref "T_L3") (pin "B") (pinfunction "B_B") (pintype "passive"))
    )
    (net (code "58") (name "Net-(RB_L4-Pad1)") (class "Default")
      (node (ref "RB_L4") (pin "1") (pinfunction "1_1") (pintype "passive"))
      (node (ref "T_L4") (pin "B") (pinfunction "B_B") (pintype "passive"))
    )
    (net (code "59") (name "Net-(RB_L5-Pad1)") (class "Default")
      (node (ref "RB_L5") (pin "1") (pinfunction "1_1") (pintype "passive"))
      (node (ref "T_L5") (pin "B") (pinfunction "B_B") (pintype "passive"))
    )
    (net (code "60") (name "Net-(RB_L6-Pad1)") (class "Default")
      (node (ref "RB_L6") (pin "1") (pinfunction "1_1") (pintype "passive"))
      (node (ref "T_L6") (pin "B") (pinfunction "B_B") (pintype "passive"))
    )
    (net (code "61") (name "Net-(RB_R1-Pad1)") (class "Default")
      (node (ref "RB_R1") (pin "1") (pinfunction "1_1") (pintype "passive"))
      (node (ref "T_R1") (pin "B") (pinfunction "B_B") (pintype "passive"))
    )
    (net (code "62") (name "Net-(RB_R2-Pad1)") (class "Default")
      (node (ref "RB_R2") (pin "1") (pinfunction "1_1") (pintype "passive"))
      (node (ref "T_R2") (pin "B") (pinfunction "B_B") (pintype "passive"))
    )
    (net (code "63") (name "Net-(RB_R3-Pad1)") (class "Default")
      (node (ref "RB_R3") (pin "1") (pinfunction "1_1") (pintype "passive"))
      (node (ref "T_R3") (pin "B") (pinfunction "B_B") (pintype "passive"))
    )
    (net (code "64") (name "Net-(RB_R4-Pad1)") (class "Default")
      (node (ref "RB_R4") (pin "1") (pinfunction "1_1") (pintype "passive"))
      (node (ref "T_R4") (pin "B") (pinfunction "B_B") (pintype "passive"))
    )
    (net (code "65") (name "Net-(RB_R5-Pad1)") (class "Default")
      (node (ref "RB_R5") (pin "1") (pinfunction "1_1") (pintype "passive"))
      (node (ref "T_R5") (pin "B") (pinfunction "B_B") (pintype "passive"))
    )
    (net (code "66") (name "Net-(RB_R6-Pad1)") (class "Default")
      (node (ref "RB_R6") (pin "1") (pinfunction "1_1") (pintype "passive"))
      (node (ref "T_R6") (pin "B") (pinfunction "B_B") (pintype "passive"))
    )
    (net (code "67") (name "VDD") (class "Default")
      (node (ref "MAIN_FUSE") (pin "PIN2") (pinfunction "PIN2_PIN2") (pintype "bidirectional"))
      (node (ref "P_D") (pin "P$1") (pinfunction "1_P$1") (pintype "passive"))
    )
    (net (code "68") (name "unconnected-(TDN3-1211WI-ON{slash}OFF-PadONOFF)") (class "Default")
      (node (ref "TDN3-1211WI") (pin "ONOFF") (pinfunction "ON/OFF_ONOFF") (pintype "bidirectional"))
    )
    (net (code "69") (name "unconnected-(TEENSY3.6-0{slash}RX1{slash}MOSI1{slash}T-Pad0)") (class "Default")
      (node (ref "TEENSY3.6") (pin "0") (pinfunction "0/RX1/MOSI1/T_0") (pintype "bidirectional"))
    )
    (net (code "70") (name "unconnected-(TEENSY3.6-1{slash}TX1{slash}MISO1{slash}T-Pad1)") (class "Default")
      (node (ref "TEENSY3.6") (pin "1") (pinfunction "1/TX1/MISO1/T_1") (pintype "bidirectional"))
    )
    (net (code "71") (name "unconnected-(TEENSY3.6-2{slash}PWM-Pad2)") (class "Default")
      (node (ref "TEENSY3.6") (pin "2") (pinfunction "2/PWM_2") (pintype "bidirectional"))
    )
    (net (code "72") (name "unconnected-(TEENSY3.6-5{slash}PWM-Pad5)") (class "Default")
      (node (ref "TEENSY3.6") (pin "5") (pinfunction "5/PWM_5") (pintype "bidirectional"))
    )
    (net (code "73") (name "unconnected-(TEENSY3.6-6{slash}PWM-Pad6)") (class "Default")
      (node (ref "TEENSY3.6") (pin "6") (pinfunction "6/PWM_6") (pintype "bidirectional"))
    )
    (net (code "74") (name "unconnected-(TEENSY3.6-20{slash}A6{slash}PWM-Pad20{slash}A6)") (class "Default")
      (node (ref "TEENSY3.6") (pin "20/A6") (pinfunction "20/A6/PWM_20/A6") (pintype "bidirectional"))
    )
    (net (code "75") (name "unconnected-(TEENSY3.6-21{slash}A7{slash}PWM-Pad21{slash}A7)") (class "Default")
      (node (ref "TEENSY3.6") (pin "21/A7") (pinfunction "21/A7/PWM_21/A7") (pintype "bidirectional"))
    )
    (net (code "76") (name "unconnected-(TEENSY3.6-22{slash}A8{slash}T{slash}PWM-Pad22{slash}A8)") (class "Default")
      (node (ref "TEENSY3.6") (pin "22/A8") (pinfunction "22/A8/T/PWM_22/A8") (pintype "bidirectional"))
    )
    (net (code "77") (name "unconnected-(TEENSY3.6-23{slash}A9{slash}T{slash}PWM-Pad23{slash}A9)") (class "Default")
      (node (ref "TEENSY3.6") (pin "23/A9") (pinfunction "23/A9/T/PWM_23/A9") (pintype "bidirectional"))
    )
    (net (code "78") (name "unconnected-(TEENSY3.6-29{slash}T{slash}PWM-Pad29)") (class "Default")
      (node (ref "TEENSY3.6") (pin "29") (pinfunction "29/T/PWM_29") (pintype "bidirectional"))
    )
    (net (code "79") (name "unconnected-(TEENSY3.6-30{slash}T{slash}PWM-Pad30)") (class "Default")
      (node (ref "TEENSY3.6") (pin "30") (pinfunction "30/T/PWM_30") (pintype "bidirectional"))
    )
    (net (code "80") (name "unconnected-(TEENSY3.6-31{slash}A12{slash}RX4-Pad31{slash}A12)") (class "Default")
      (node (ref "TEENSY3.6") (pin "31/A12") (pinfunction "31/A12/RX4_31/A12") (pintype "bidirectional"))
    )
    (net (code "81") (name "unconnected-(TEENSY3.6-32{slash}A13{slash}TX4-Pad32{slash}A13)") (class "Default")
      (node (ref "TEENSY3.6") (pin "32/A13") (pinfunction "32/A13/TX4_32/A13") (pintype "bidirectional"))
    )
    (net (code "82") (name "unconnected-(TEENSY3.6-34{slash}A15{slash}RX5{slash}CAN1-RX-Pad34{slash}A15)") (class "Default")
      (node (ref "TEENSY3.6") (pin "34/A15") (pinfunction "34/A15/RX5/CAN1-RX_34/A15") (pintype "bidirectional"))
    )
    (net (code "83") (name "unconnected-(TEENSY3.6-35{slash}A16{slash}PWM-Pad35{slash}A16)") (class "Default")
      (node (ref "TEENSY3.6") (pin "35/A16") (pinfunction "35/A16/PWM_35/A16") (pintype "bidirectional"))
    )
    (net (code "84") (name "unconnected-(TEENSY3.6-36{slash}A17{slash}PWM-Pad36{slash}A17)") (class "Default")
      (node (ref "TEENSY3.6") (pin "36/A17") (pinfunction "36/A17/PWM_36/A17") (pintype "bidirectional"))
    )
    (net (code "85") (name "unconnected-(TEENSY3.6-37{slash}A18{slash}SCL1{slash}PWM-Pad37{slash}A18)") (class "Default")
      (node (ref "TEENSY3.6") (pin "37/A18") (pinfunction "37/A18/SCL1/PWM_37/A18") (pintype "bidirectional"))
    )
    (net (code "86") (name "unconnected-(TEENSY3.6-38{slash}A19{slash}SDA1{slash}PWM-Pad38{slash}A19)") (class "Default")
      (node (ref "TEENSY3.6") (pin "38/A19") (pinfunction "38/A19/SDA1/PWM_38/A19") (pintype "bidirectional"))
    )
    (net (code "87") (name "unconnected-(TEENSY3.6-A21{slash}DAC0-PadA21)") (class "Default")
      (node (ref "TEENSY3.6") (pin "A21") (pinfunction "A21/DAC0_A21") (pintype "bidirectional"))
    )
    (net (code "88") (name "unconnected-(TEENSY3.6-A22{slash}DAC1-PadA22)") (class "Default")
      (node (ref "TEENSY3.6") (pin "A22") (pinfunction "A22/DAC1_A22") (pintype "bidirectional"))
    )
    (net (code "89") (name "unconnected-(TEENSY3.6-Pad24)") (class "Default")
      (node (ref "TEENSY3.6") (pin "24") (pinfunction "24_24") (pintype "bidirectional"))
    )
    (net (code "90") (name "unconnected-(TEENSY3.6-Pad25)") (class "Default")
      (node (ref "TEENSY3.6") (pin "25") (pinfunction "25_25") (pintype "bidirectional"))
    )
    (net (code "91") (name "unconnected-(TEENSY3.6-Pad26)") (class "Default")
      (node (ref "TEENSY3.6") (pin "26") (pinfunction "26_26") (pintype "bidirectional"))
    )
    (net (code "92") (name "unconnected-(TEENSY3.6-Pad27)") (class "Default")
      (node (ref "TEENSY3.6") (pin "27") (pinfunction "27_27") (pintype "bidirectional"))
    )
    (net (code "93") (name "unconnected-(TEENSY3.6-Pad28)") (class "Default")
      (node (ref "TEENSY3.6") (pin "28") (pinfunction "28_28") (pintype "bidirectional"))
    )
    (net (code "94") (name "unconnected-(TEENSY3.6-Pad39{slash}A20)") (class "Default")
      (node (ref "TEENSY3.6") (pin "39/A20") (pinfunction "39/A20_39/A20") (pintype "bidirectional"))
    )
  )
)
